# design.net
KiCad netlist of a schematic drawn in Altium Designer
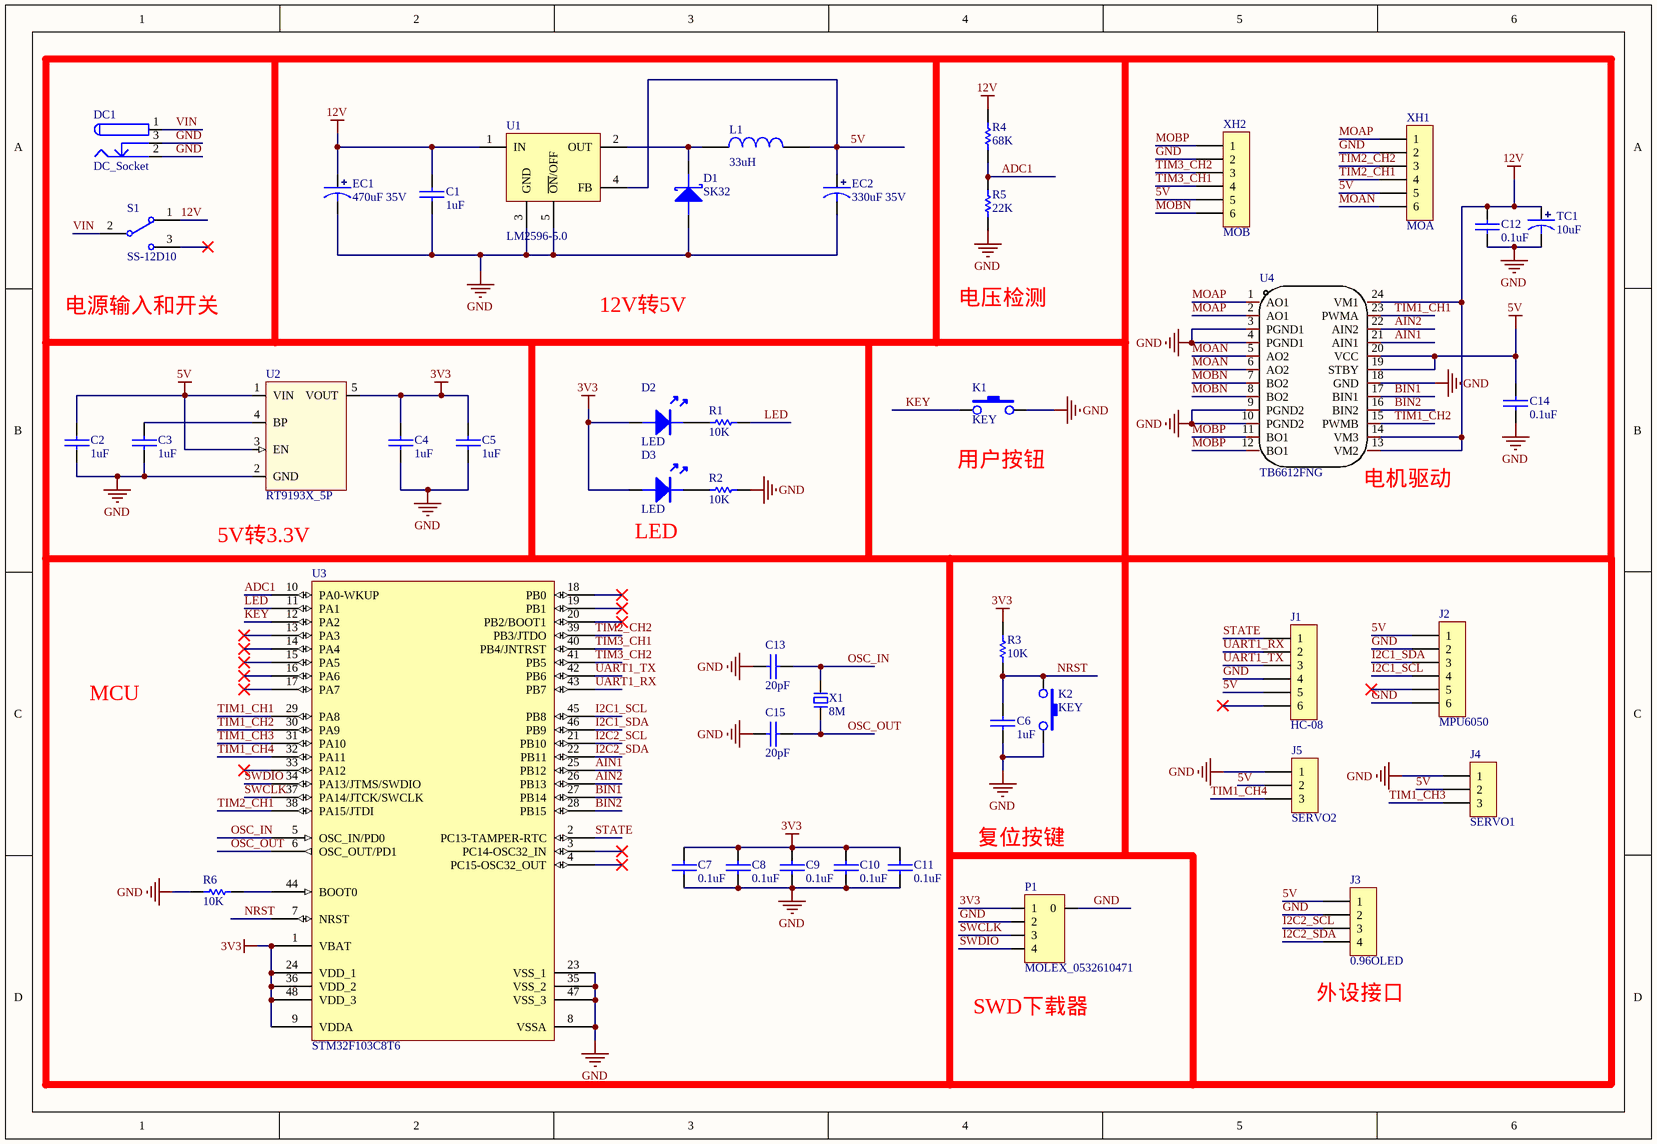
[diagram p0: 平衡车驱动板.SchDoc]

(export (version "E")
  (design (tool "Eeschema 10.0.6"))
  (components
    (comp (ref "C1")
      (value "1uF")
      (footprint "0603C")
      (description "无极性电容")
      (libsource (lib "电容") (part "CAP"))
    )
    (comp (ref "C2")
      (value "1uF")
      (footprint "0603C")
      (description "无极性电容")
      (libsource (lib "电容") (part "CAP"))
    )
    (comp (ref "C3")
      (value "1uF")
      (footprint "0603C")
      (description "无极性电容")
      (libsource (lib "电容") (part "CAP"))
    )
    (comp (ref "C4")
      (value "1uF")
      (footprint "0603C")
      (description "无极性电容")
      (libsource (lib "电容") (part "CAP"))
    )
    (comp (ref "C5")
      (value "1uF")
      (footprint "0603C")
      (description "无极性电容")
      (libsource (lib "电容") (part "CAP"))
    )
    (comp (ref "C6")
      (value "1uF")
      (footprint "0603C")
      (description "无极性电容")
      (libsource (lib "电容") (part "CAP"))
    )
    (comp (ref "C7")
      (value "0.1uF")
      (footprint "0603C")
      (description "无极性电容")
      (libsource (lib "电容") (part "CAP"))
    )
    (comp (ref "C8")
      (value "0.1uF")
      (footprint "0603C")
      (description "无极性电容")
      (libsource (lib "电容") (part "CAP"))
    )
    (comp (ref "C9")
      (value "0.1uF")
      (footprint "0603C")
      (description "无极性电容")
      (libsource (lib "电容") (part "CAP"))
    )
    (comp (ref "C10")
      (value "0.1uF")
      (footprint "0603C")
      (description "无极性电容")
      (libsource (lib "电容") (part "CAP"))
    )
    (comp (ref "C11")
      (value "0.1uF")
      (footprint "0603C")
      (description "无极性电容")
      (libsource (lib "电容") (part "CAP"))
    )
    (comp (ref "C12")
      (value "0.1uF")
      (footprint "0603C")
      (description "无极性电容")
      (libsource (lib "电容") (part "CAP"))
    )
    (comp (ref "C13")
      (value "20pF")
      (footprint "0603C")
      (description "无极性电容")
      (libsource (lib "电容") (part "CAP"))
    )
    (comp (ref "C14")
      (value "0.1uF")
      (footprint "0603C")
      (description "无极性电容")
      (libsource (lib "电容") (part "CAP"))
    )
    (comp (ref "C15")
      (value "20pF")
      (footprint "0603C")
      (description "无极性电容")
      (libsource (lib "电容") (part "CAP"))
    )
    (comp (ref "D1")
      (value "SK32")
      (footprint "SOD-123")
      (description "肖特基二极管")
      (libsource (lib "二极管") (part "DIODE SCHOTTKY"))
    )
    (comp (ref "D2") (value "LED") (footprint "LED-0805B") (libsource (lib "LED") (part "LED")))
    (comp (ref "D3") (value "LED") (footprint "LED-0805B") (libsource (lib "LED") (part "LED")))
    (comp (ref "DC1") (value "DC_Socket") (footprint "DC-050") (libsource (lib "电源插座") (part "DC_Socket")))
    (comp (ref "EC1")
      (value "470uF 35V")
      (footprint "SMD-EC10X10X10")
      (description "贴片电解电容")
      (libsource (lib "电容") (part "SMD_ECAP"))
    )
    (comp (ref "EC2")
      (value "330uF 35V")
      (footprint "SMD-EC10X10X10")
      (description "贴片电解电容")
      (libsource (lib "电容") (part "SMD_ECAP"))
    )
    (comp (ref "J1")
      (value "HC-08")
      (footprint "Fe-HDR1X6/2.54-S")
      (libsource (lib "排母") (part "Female HDR1X6"))
    )
    (comp (ref "J2")
      (value "MPU6050")
      (footprint "Fe-HDR1X6/2.54-S")
      (libsource (lib "排母") (part "Female HDR1X6"))
    )
    (comp (ref "J3")
      (value "0.96OLED")
      (footprint "Fe-HDR1X4/2.54-S")
      (libsource (lib "排母") (part "Female HDR1X4"))
    )
    (comp (ref "J4")
      (value "SERVO1")
      (footprint "Pin HDR1X3/2.54mm-S")
      (libsource (lib "排针") (part "Pin HDR1X3"))
    )
    (comp (ref "J5")
      (value "SERVO2")
      (footprint "Pin HDR1X3/2.54mm-S")
      (libsource (lib "排针") (part "Pin HDR1X3"))
    )
    (comp (ref "K1") (value "KEY") (footprint "SMD-3X6X2.5") (libsource (lib "轻触开关") (part "KEY")))
    (comp (ref "K2") (value "KEY") (footprint "SMD-3X6X2.5") (libsource (lib "轻触开关") (part "KEY")))
    (comp (ref "L1")
      (value "33uH")
      (footprint "0630L")
      (description "INDUCTOR")
      (libsource (lib "电感") (part "INDUCTOR"))
    )
    (comp (ref "P1")
      (value "MOLEX_0532610471")
      (footprint "MOLEX 0532610471")
      (description "MOLEX_0532610471,4Pin,1.25mm")
      (libsource (lib "MOLEX_053261") (part "MOLEX_0532610471"))
    )
    (comp (ref "R1") (value "10K") (footprint "0603R") (libsource (lib "电阻") (part "RES")))
    (comp (ref "R2") (value "10K") (footprint "0603R") (libsource (lib "电阻") (part "RES")))
    (comp (ref "R3") (value "10K") (footprint "0603R") (libsource (lib "电阻") (part "RES")))
    (comp (ref "R4") (value "68K") (footprint "0603R") (libsource (lib "电阻") (part "RES")))
    (comp (ref "R5") (value "22K") (footprint "0603R") (libsource (lib "电阻") (part "RES")))
    (comp (ref "R6") (value "10K") (footprint "0603R") (libsource (lib "电阻") (part "RES")))
    (comp (ref "S1") (value "SS-12D10") (footprint "SS-12D10") (libsource (lib "电源开关") (part "SS-12D10")))
    (comp (ref "TC1")
      (value "10uF")
      (footprint "TAJ-B/3528")
      (description "钽电容")
      (libsource (lib "电容") (part "TCAP"))
    )
    (comp (ref "U1")
      (value "LM2596-5.0")
      (footprint "TO263-5A")
      (description "DC降压芯片")
      (libsource (lib "电源芯片") (part "LM2596-5.0"))
    )
    (comp (ref "U2")
      (value "RT9193X_5P")
      (footprint "SOT23-5L")
      (description "5V转3.3V")
      (libsource (lib "下推式磁悬浮") (part "RT9193X_5P"))
    )
    (comp (ref "U3")
      (value "STM32F103C8T6")
      (footprint "LQFP48 7X7")
      (libsource (lib "STM32系列") (part "STM32F103C8T6"))
    )
    (comp (ref "U4")
      (value "TB6612FNG")
      (footprint "TB6612-SSOP-24")
      (description "双电机驱动")
      (libsource (lib "下推式磁悬浮") (part "TB6612FNG"))
    )
    (comp (ref "X1")
      (value "8M")
      (footprint "OSC HC-49S")
      (description "2脚无源脚晶振")
      (libsource (lib "晶振") (part "XTAL-2P"))
    )
    (comp (ref "XH1") (value "MOA") (footprint "XH6/2.54mm/90") (libsource (lib "XH，VH") (part "XH6")))
    (comp (ref "XH2") (value "MOB") (footprint "XH6/2.54mm/90") (libsource (lib "XH，VH") (part "XH6")))
  )
  (nets
    (net (code "1") (name "/ADC1") (class "Default")
      (node (ref "R4") (pin "1") (pinfunction "1_1") (pintype "passive"))
      (node (ref "R5") (pin "2") (pinfunction "2_2") (pintype "passive"))
      (node (ref "U3") (pin "10") (pinfunction "PA0-WKUP_10") (pintype "bidirectional"))
    )
    (net (code "2") (name "/AIN1") (class "Default")
      (node (ref "U3") (pin "25") (pinfunction "PB12_25") (pintype "bidirectional"))
      (node (ref "U4") (pin "21") (pinfunction "AIN1_21") (pintype "passive"))
    )
    (net (code "3") (name "/AIN2") (class "Default")
      (node (ref "U3") (pin "26") (pinfunction "PB13_26") (pintype "bidirectional"))
      (node (ref "U4") (pin "22") (pinfunction "AIN2_22") (pintype "passive"))
    )
    (net (code "4") (name "/BIN1") (class "Default")
      (node (ref "U3") (pin "27") (pinfunction "PB14_27") (pintype "bidirectional"))
      (node (ref "U4") (pin "17") (pinfunction "BIN1_17") (pintype "passive"))
    )
    (net (code "5") (name "/BIN2") (class "Default")
      (node (ref "U3") (pin "28") (pinfunction "PB15_28") (pintype "bidirectional"))
      (node (ref "U4") (pin "16") (pinfunction "BIN2_16") (pintype "passive"))
    )
    (net (code "6") (name "/I2C1_SCL") (class "Default")
      (node (ref "J2") (pin "4") (pinfunction "4_4") (pintype "passive"))
      (node (ref "U3") (pin "45") (pinfunction "PB8_45") (pintype "bidirectional"))
    )
    (net (code "7") (name "/I2C1_SDA") (class "Default")
      (node (ref "J2") (pin "3") (pinfunction "3_3") (pintype "passive"))
      (node (ref "U3") (pin "46") (pinfunction "PB9_46") (pintype "bidirectional"))
    )
    (net (code "8") (name "/I2C2_SCL") (class "Default")
      (node (ref "J3") (pin "3") (pinfunction "3_3") (pintype "passive"))
      (node (ref "U3") (pin "21") (pinfunction "PB10_21") (pintype "bidirectional"))
    )
    (net (code "9") (name "/I2C2_SDA") (class "Default")
      (node (ref "J3") (pin "4") (pinfunction "4_4") (pintype "passive"))
      (node (ref "U3") (pin "22") (pinfunction "PB11_22") (pintype "bidirectional"))
    )
    (net (code "10") (name "/KEY") (class "Default")
      (node (ref "K1") (pin "1") (pinfunction "1_1") (pintype "passive"))
      (node (ref "U3") (pin "12") (pinfunction "PA2_12") (pintype "bidirectional"))
    )
    (net (code "11") (name "/LED") (class "Default")
      (node (ref "R1") (pin "2") (pinfunction "2_2") (pintype "passive"))
      (node (ref "U3") (pin "11") (pinfunction "PA1_11") (pintype "bidirectional"))
    )
    (net (code "12") (name "/MOAN") (class "Default")
      (node (ref "U4") (pin "5") (pinfunction "AO2_5") (pintype "passive"))
      (node (ref "U4") (pin "6") (pinfunction "AO2_6") (pintype "passive"))
      (node (ref "XH1") (pin "6") (pinfunction "6_6") (pintype "passive"))
    )
    (net (code "13") (name "/MOAP") (class "Default")
      (node (ref "U4") (pin "1") (pinfunction "AO1_1") (pintype "passive"))
      (node (ref "U4") (pin "2") (pinfunction "AO1_2") (pintype "passive"))
      (node (ref "XH1") (pin "1") (pinfunction "1_1") (pintype "passive"))
    )
    (net (code "14") (name "/MOBN") (class "Default")
      (node (ref "U4") (pin "7") (pinfunction "BO2_7") (pintype "passive"))
      (node (ref "U4") (pin "8") (pinfunction "BO2_8") (pintype "passive"))
      (node (ref "XH2") (pin "6") (pinfunction "6_6") (pintype "passive"))
    )
    (net (code "15") (name "/MOBP") (class "Default")
      (node (ref "U4") (pin "11") (pinfunction "BO1_11") (pintype "passive"))
      (node (ref "U4") (pin "12") (pinfunction "BO1_12") (pintype "passive"))
      (node (ref "XH2") (pin "1") (pinfunction "1_1") (pintype "passive"))
    )
    (net (code "16") (name "/NRST") (class "Default")
      (node (ref "C6") (pin "2") (pinfunction "2_2") (pintype "passive"))
      (node (ref "K2") (pin "1") (pinfunction "1_1") (pintype "passive"))
      (node (ref "R3") (pin "2") (pinfunction "2_2") (pintype "passive"))
      (node (ref "U3") (pin "7") (pinfunction "NRST_7") (pintype "bidirectional"))
    )
    (net (code "17") (name "/OSC_IN") (class "Default")
      (node (ref "C13") (pin "2") (pinfunction "2_2") (pintype "passive"))
      (node (ref "U3") (pin "5") (pinfunction "OSC_IN/PD0_5") (pintype "input"))
      (node (ref "X1") (pin "2") (pinfunction "2_2") (pintype "passive"))
    )
    (net (code "18") (name "/OSC_OUT") (class "Default")
      (node (ref "C15") (pin "2") (pinfunction "2_2") (pintype "passive"))
      (node (ref "U3") (pin "6") (pinfunction "OSC_OUT/PD1_6") (pintype "output"))
      (node (ref "X1") (pin "1") (pinfunction "1_1") (pintype "passive"))
    )
    (net (code "19") (name "/STATE") (class "Default")
      (node (ref "J1") (pin "1") (pinfunction "1_1") (pintype "passive"))
      (node (ref "U3") (pin "2") (pinfunction "PC13-TAMPER-RTC_2") (pintype "bidirectional"))
    )
    (net (code "20") (name "/SWCLK") (class "Default")
      (node (ref "P1") (pin "3") (pinfunction "3_3") (pintype "passive"))
      (node (ref "U3") (pin "37") (pinfunction "PA14/JTCK/SWCLK_37") (pintype "bidirectional"))
    )
    (net (code "21") (name "/SWDIO") (class "Default")
      (node (ref "P1") (pin "4") (pinfunction "4_4") (pintype "passive"))
      (node (ref "U3") (pin "34") (pinfunction "PA13/JTMS/SWDIO_34") (pintype "bidirectional"))
    )
    (net (code "22") (name "/TIM1_CH1") (class "Default")
      (node (ref "U3") (pin "29") (pinfunction "PA8_29") (pintype "bidirectional"))
      (node (ref "U4") (pin "23") (pinfunction "PWMA_23") (pintype "passive"))
    )
    (net (code "23") (name "/TIM1_CH2") (class "Default")
      (node (ref "U3") (pin "30") (pinfunction "PA9_30") (pintype "bidirectional"))
      (node (ref "U4") (pin "15") (pinfunction "PWMB_15") (pintype "passive"))
    )
    (net (code "24") (name "/TIM1_CH3") (class "Default")
      (node (ref "J4") (pin "3") (pinfunction "3_3") (pintype "passive"))
      (node (ref "U3") (pin "31") (pinfunction "PA10_31") (pintype "bidirectional"))
    )
    (net (code "25") (name "/TIM1_CH4") (class "Default")
      (node (ref "J5") (pin "3") (pinfunction "3_3") (pintype "passive"))
      (node (ref "U3") (pin "32") (pinfunction "PA11_32") (pintype "bidirectional"))
    )
    (net (code "26") (name "/TIM2_CH1") (class "Default")
      (node (ref "U3") (pin "38") (pinfunction "PA15/JTDI_38") (pintype "bidirectional"))
      (node (ref "XH1") (pin "4") (pinfunction "4_4") (pintype "passive"))
    )
    (net (code "27") (name "/TIM2_CH2") (class "Default")
      (node (ref "U3") (pin "39") (pinfunction "PB3/JTDO_39") (pintype "bidirectional"))
      (node (ref "XH1") (pin "3") (pinfunction "3_3") (pintype "passive"))
    )
    (net (code "28") (name "/TIM3_CH1") (class "Default")
      (node (ref "U3") (pin "40") (pinfunction "PB4/JNTRST_40") (pintype "bidirectional"))
      (node (ref "XH2") (pin "4") (pinfunction "4_4") (pintype "passive"))
    )
    (net (code "29") (name "/TIM3_CH2") (class "Default")
      (node (ref "U3") (pin "41") (pinfunction "PB5_41") (pintype "bidirectional"))
      (node (ref "XH2") (pin "3") (pinfunction "3_3") (pintype "passive"))
    )
    (net (code "30") (name "/UART1_RX") (class "Default")
      (node (ref "J1") (pin "2") (pinfunction "2_2") (pintype "passive"))
      (node (ref "U3") (pin "43") (pinfunction "PB7_43") (pintype "bidirectional"))
    )
    (net (code "31") (name "/UART1_TX") (class "Default")
      (node (ref "J1") (pin "3") (pinfunction "3_3") (pintype "passive"))
      (node (ref "U3") (pin "42") (pinfunction "PB6_42") (pintype "bidirectional"))
    )
    (net (code "32") (name "/VIN") (class "Default")
      (node (ref "DC1") (pin "1") (pinfunction "1_1") (pintype "power_in"))
      (node (ref "S1") (pin "2") (pinfunction "2_2") (pintype "passive"))
    )
    (net (code "33") (name "3V3") (class "Default")
      (node (ref "C10") (pin "2") (pinfunction "2_2") (pintype "passive"))
      (node (ref "C11") (pin "2") (pinfunction "2_2") (pintype "passive"))
      (node (ref "C4") (pin "2") (pinfunction "2_2") (pintype "passive"))
      (node (ref "C5") (pin "2") (pinfunction "2_2") (pintype "passive"))
      (node (ref "C7") (pin "2") (pinfunction "2_2") (pintype "passive"))
      (node (ref "C8") (pin "2") (pinfunction "2_2") (pintype "passive"))
      (node (ref "C9") (pin "2") (pinfunction "2_2") (pintype "passive"))
      (node (ref "D2") (pin "A") (pinfunction "A_A") (pintype "passive"))
      (node (ref "D3") (pin "A") (pinfunction "A_A") (pintype "passive"))
      (node (ref "P1") (pin "1") (pinfunction "1_1") (pintype "passive"))
      (node (ref "R3") (pin "1") (pinfunction "1_1") (pintype "passive"))
      (node (ref "U2") (pin "5") (pinfunction "VOUT_5") (pintype "power_in"))
      (node (ref "U3") (pin "1") (pinfunction "VBAT_1") (pintype "power_in"))
      (node (ref "U3") (pin "24") (pinfunction "VDD_1_24") (pintype "power_in"))
      (node (ref "U3") (pin "36") (pinfunction "VDD_2_36") (pintype "power_in"))
      (node (ref "U3") (pin "48") (pinfunction "VDD_3_48") (pintype "power_in"))
      (node (ref "U3") (pin "9") (pinfunction "VDDA_9") (pintype "power_in"))
    )
    (net (code "34") (name "5V") (class "Default")
      (node (ref "C14") (pin "2") (pinfunction "2_2") (pintype "passive"))
      (node (ref "C2") (pin "2") (pinfunction "2_2") (pintype "passive"))
      (node (ref "EC2") (pin "1") (pinfunction "1_1") (pintype "passive"))
      (node (ref "J1") (pin "5") (pinfunction "5_5") (pintype "passive"))
      (node (ref "J2") (pin "1") (pinfunction "1_1") (pintype "passive"))
      (node (ref "J3") (pin "1") (pinfunction "1_1") (pintype "passive"))
      (node (ref "J4") (pin "2") (pinfunction "2_2") (pintype "passive"))
      (node (ref "J5") (pin "2") (pinfunction "2_2") (pintype "passive"))
      (node (ref "L1") (pin "2") (pinfunction "2_2") (pintype "passive"))
      (node (ref "U1") (pin "4") (pinfunction "FB_4") (pintype "passive"))
      (node (ref "U2") (pin "1") (pinfunction "VIN_1") (pintype "power_in"))
      (node (ref "U2") (pin "3") (pinfunction "EN_3") (pintype "input"))
      (node (ref "U4") (pin "19") (pinfunction "STBY_19") (pintype "passive"))
      (node (ref "U4") (pin "20") (pinfunction "VCC_20") (pintype "passive"))
      (node (ref "XH1") (pin "5") (pinfunction "5_5") (pintype "passive"))
      (node (ref "XH2") (pin "5") (pinfunction "5_5") (pintype "passive"))
    )
    (net (code "35") (name "12V") (class "Default")
      (node (ref "C1") (pin "2") (pinfunction "2_2") (pintype "passive"))
      (node (ref "C12") (pin "2") (pinfunction "2_2") (pintype "passive"))
      (node (ref "EC1") (pin "1") (pinfunction "1_1") (pintype "passive"))
      (node (ref "R4") (pin "2") (pinfunction "2_2") (pintype "passive"))
      (node (ref "S1") (pin "1") (pinfunction "1_1") (pintype "passive"))
      (node (ref "TC1") (pin "1") (pinfunction "1_1") (pintype "passive"))
      (node (ref "U1") (pin "1") (pinfunction "IN_1") (pintype "power_in"))
      (node (ref "U4") (pin "13") (pinfunction "VM2_13") (pintype "passive"))
      (node (ref "U4") (pin "14") (pinfunction "VM3_14") (pintype "passive"))
      (node (ref "U4") (pin "24") (pinfunction "VM1_24") (pintype "passive"))
    )
    (net (code "36") (name "GND") (class "Default")
      (node (ref "C1") (pin "1") (pinfunction "1_1") (pintype "passive"))
      (node (ref "C10") (pin "1") (pinfunction "1_1") (pintype "passive"))
      (node (ref "C11") (pin "1") (pinfunction "1_1") (pintype "passive"))
      (node (ref "C12") (pin "1") (pinfunction "1_1") (pintype "passive"))
      (node (ref "C13") (pin "1") (pinfunction "1_1") (pintype "passive"))
      (node (ref "C14") (pin "1") (pinfunction "1_1") (pintype "passive"))
      (node (ref "C15") (pin "1") (pinfunction "1_1") (pintype "passive"))
      (node (ref "C2") (pin "1") (pinfunction "1_1") (pintype "passive"))
      (node (ref "C3") (pin "1") (pinfunction "1_1") (pintype "passive"))
      (node (ref "C4") (pin "1") (pinfunction "1_1") (pintype "passive"))
      (node (ref "C5") (pin "1") (pinfunction "1_1") (pintype "passive"))
      (node (ref "C6") (pin "1") (pinfunction "1_1") (pintype "passive"))
      (node (ref "C7") (pin "1") (pinfunction "1_1") (pintype "passive"))
      (node (ref "C8") (pin "1") (pinfunction "1_1") (pintype "passive"))
      (node (ref "C9") (pin "1") (pinfunction "1_1") (pintype "passive"))
      (node (ref "D1") (pin "A") (pinfunction "A_A") (pintype "passive"))
      (node (ref "DC1") (pin "2") (pinfunction "2_2") (pintype "power_in"))
      (node (ref "DC1") (pin "3") (pinfunction "3_3") (pintype "power_in"))
      (node (ref "EC1") (pin "2") (pinfunction "2_2") (pintype "passive"))
      (node (ref "EC2") (pin "2") (pinfunction "2_2") (pintype "passive"))
      (node (ref "J1") (pin "4") (pinfunction "4_4") (pintype "passive"))
      (node (ref "J2") (pin "2") (pinfunction "2_2") (pintype "passive"))
      (node (ref "J2") (pin "6") (pinfunction "6_6") (pintype "passive"))
      (node (ref "J3") (pin "2") (pinfunction "2_2") (pintype "passive"))
      (node (ref "J4") (pin "1") (pinfunction "1_1") (pintype "passive"))
      (node (ref "J5") (pin "1") (pinfunction "1_1") (pintype "passive"))
      (node (ref "K1") (pin "3") (pinfunction "3_3") (pintype "passive"))
      (node (ref "K2") (pin "3") (pinfunction "3_3") (pintype "passive"))
      (node (ref "P1") (pin "2") (pinfunction "2_2") (pintype "passive"))
      (node (ref "P1") (pin "SH") (pinfunction "0_SH") (pintype "passive"))
      (node (ref "R2") (pin "2") (pinfunction "2_2") (pintype "passive"))
      (node (ref "R5") (pin "1") (pinfunction "1_1") (pintype "passive"))
      (node (ref "R6") (pin "2") (pinfunction "2_2") (pintype "passive"))
      (node (ref "TC1") (pin "2") (pinfunction "2_2") (pintype "passive"))
      (node (ref "U1") (pin "3") (pinfunction "GND_3") (pintype "power_in"))
      (node (ref "U1") (pin "5") (pinfunction "~{ON}/OFF_5") (pintype "passive"))
      (node (ref "U2") (pin "2") (pinfunction "GND_2") (pintype "power_in"))
      (node (ref "U3") (pin "23") (pinfunction "VSS_1_23") (pintype "power_in"))
      (node (ref "U3") (pin "35") (pinfunction "VSS_2_35") (pintype "power_in"))
      (node (ref "U3") (pin "47") (pinfunction "VSS_3_47") (pintype "power_in"))
      (node (ref "U3") (pin "8") (pinfunction "VSSA_8") (pintype "power_in"))
      (node (ref "U4") (pin "10") (pinfunction "PGND2_10") (pintype "passive"))
      (node (ref "U4") (pin "18") (pinfunction "GND_18") (pintype "passive"))
      (node (ref "U4") (pin "3") (pinfunction "PGND1_3") (pintype "passive"))
      (node (ref "U4") (pin "4") (pinfunction "PGND1_4") (pintype "passive"))
      (node (ref "U4") (pin "9") (pinfunction "PGND2_9") (pintype "passive"))
      (node (ref "XH1") (pin "2") (pinfunction "2_2") (pintype "passive"))
      (node (ref "XH2") (pin "2") (pinfunction "2_2") (pintype "passive"))
    )
    (net (code "37") (name "Net-(D2-PadK)") (class "Default")
      (node (ref "D2") (pin "K") (pinfunction "K_K") (pintype "passive"))
      (node (ref "R1") (pin "1") (pinfunction "1_1") (pintype "passive"))
    )
    (net (code "38") (name "Net-(D3-PadK)") (class "Default")
      (node (ref "D3") (pin "K") (pinfunction "K_K") (pintype "passive"))
      (node (ref "R2") (pin "1") (pinfunction "1_1") (pintype "passive"))
    )
    (net (code "39") (name "Net-(U1-OUT)") (class "Default")
      (node (ref "D1") (pin "K") (pinfunction "K_K") (pintype "passive"))
      (node (ref "L1") (pin "1") (pinfunction "1_1") (pintype "passive"))
      (node (ref "U1") (pin "2") (pinfunction "OUT_2") (pintype "power_in"))
    )
    (net (code "40") (name "Net-(U2-BP)") (class "Default")
      (node (ref "C3") (pin "2") (pinfunction "2_2") (pintype "passive"))
      (node (ref "U2") (pin "4") (pinfunction "BP_4") (pintype "passive"))
    )
    (net (code "41") (name "Net-(U3-BOOT0)") (class "Default")
      (node (ref "R6") (pin "1") (pinfunction "1_1") (pintype "passive"))
      (node (ref "U3") (pin "44") (pinfunction "BOOT0_44") (pintype "input"))
    )
    (net (code "42") (name "unconnected-(J1-Pad6)") (class "Default")
      (node (ref "J1") (pin "6") (pinfunction "6_6") (pintype "passive+no_connect"))
    )
    (net (code "43") (name "unconnected-(J2-Pad5)") (class "Default")
      (node (ref "J2") (pin "5") (pinfunction "5_5") (pintype "passive+no_connect"))
    )
    (net (code "44") (name "unconnected-(S1-Pad3)") (class "Default")
      (node (ref "S1") (pin "3") (pinfunction "3_3") (pintype "passive+no_connect"))
    )
    (net (code "45") (name "unconnected-(U3-PA3-Pad13)") (class "Default")
      (node (ref "U3") (pin "13") (pinfunction "PA3_13") (pintype "bidirectional+no_connect"))
    )
    (net (code "46") (name "unconnected-(U3-PA4-Pad14)") (class "Default")
      (node (ref "U3") (pin "14") (pinfunction "PA4_14") (pintype "bidirectional+no_connect"))
    )
    (net (code "47") (name "unconnected-(U3-PA5-Pad15)") (class "Default")
      (node (ref "U3") (pin "15") (pinfunction "PA5_15") (pintype "bidirectional+no_connect"))
    )
    (net (code "48") (name "unconnected-(U3-PA6-Pad16)") (class "Default")
      (node (ref "U3") (pin "16") (pinfunction "PA6_16") (pintype "bidirectional+no_connect"))
    )
    (net (code "49") (name "unconnected-(U3-PA7-Pad17)") (class "Default")
      (node (ref "U3") (pin "17") (pinfunction "PA7_17") (pintype "bidirectional+no_connect"))
    )
    (net (code "50") (name "unconnected-(U3-PA12-Pad33)") (class "Default")
      (node (ref "U3") (pin "33") (pinfunction "PA12_33") (pintype "bidirectional+no_connect"))
    )
    (net (code "51") (name "unconnected-(U3-PB0-Pad18)") (class "Default")
      (node (ref "U3") (pin "18") (pinfunction "PB0_18") (pintype "bidirectional+no_connect"))
    )
    (net (code "52") (name "unconnected-(U3-PB1-Pad19)") (class "Default")
      (node (ref "U3") (pin "19") (pinfunction "PB1_19") (pintype "bidirectional+no_connect"))
    )
    (net (code "53") (name "unconnected-(U3-PB2{slash}BOOT1-Pad20)") (class "Default")
      (node (ref "U3") (pin "20") (pinfunction "PB2/BOOT1_20") (pintype "bidirectional+no_connect"))
    )
    (net (code "54") (name "unconnected-(U3-PC14-OSC32_IN-Pad3)") (class "Default")
      (node (ref "U3") (pin "3") (pinfunction "PC14-OSC32_IN_3") (pintype "bidirectional+no_connect"))
    )
    (net (code "55") (name "unconnected-(U3-PC15-OSC32_OUT-Pad4)") (class "Default")
      (node (ref "U3") (pin "4") (pinfunction "PC15-OSC32_OUT_4") (pintype "bidirectional+no_connect"))
    )
  )
)
